# tc264_miniv3_1.net
KiCad netlist of a schematic drawn in EasyEDA Pro
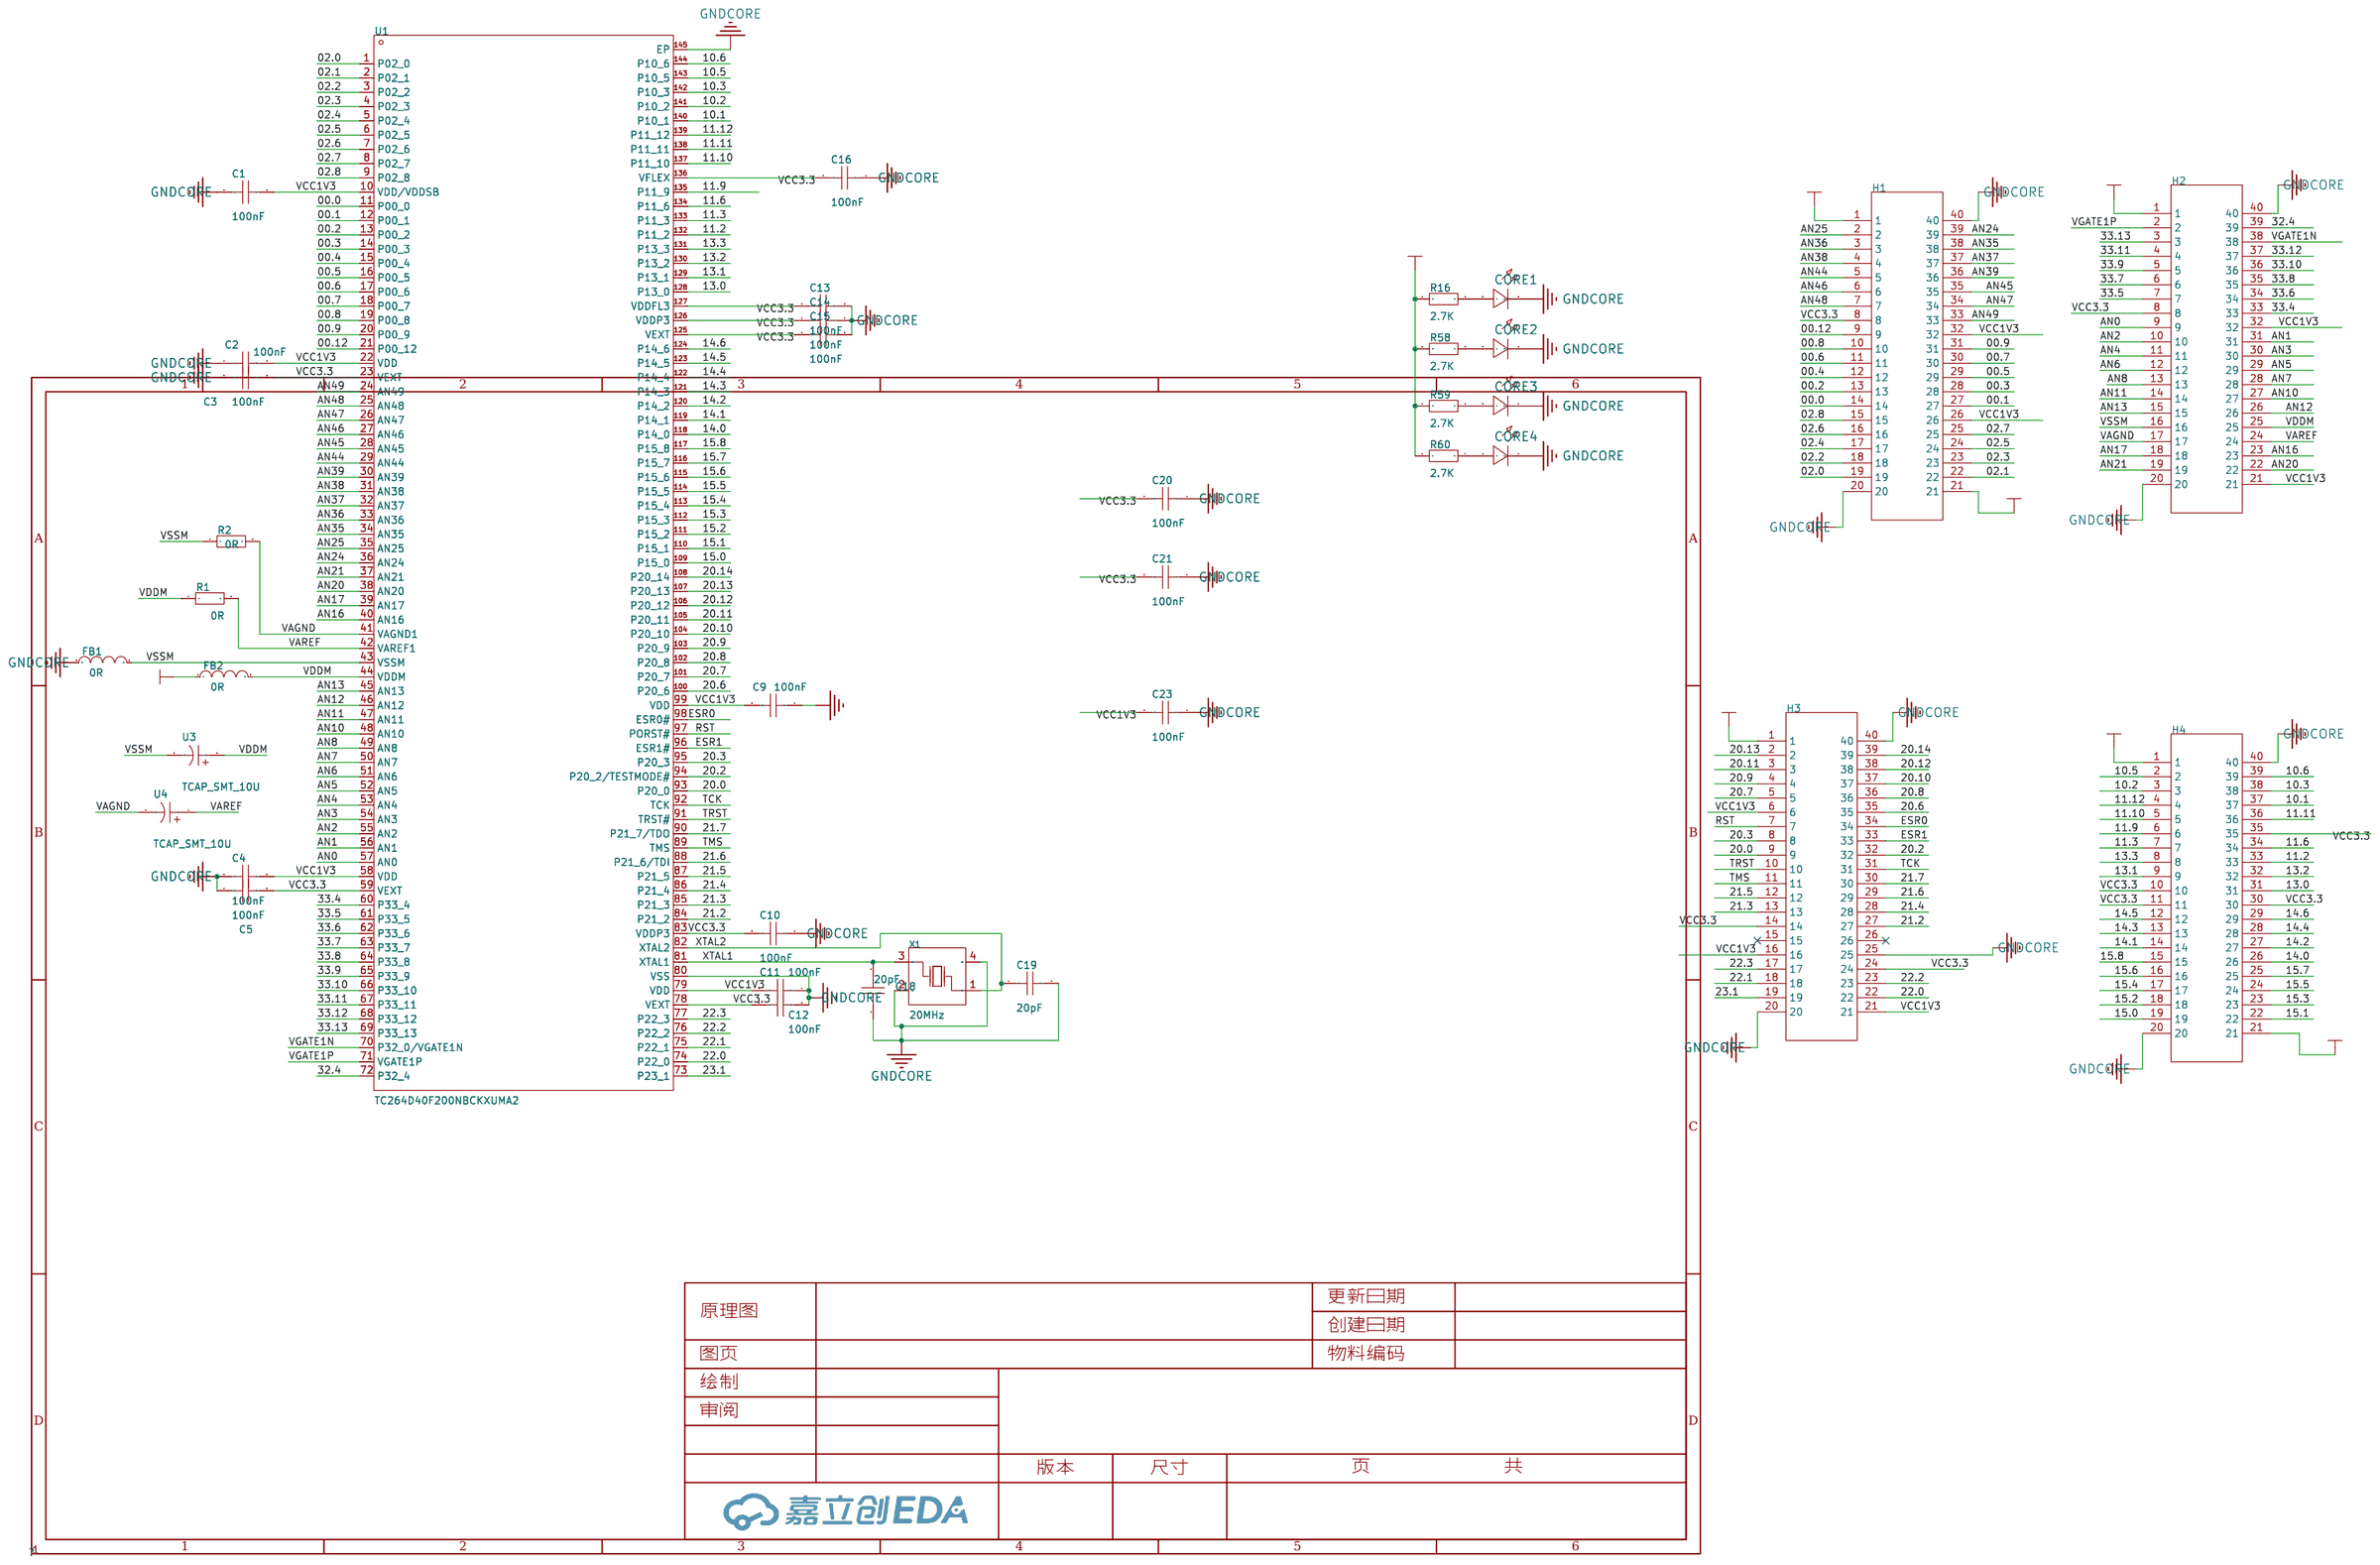
[diagram p0: schematic sheet]

(export (version "E")
  (design (tool "Eeschema 10.0.6"))
  (components
    (comp (ref "C1")
      (value "100nF")
      (footprint "easyedapro:C0603")
      (libsource (lib "easyedapro") (part "CapAcitance"))
    )
    (comp (ref "C2")
      (value "100nF")
      (footprint "easyedapro:C0603")
      (libsource (lib "easyedapro") (part "CapAcitance"))
    )
    (comp (ref "C3")
      (value "100nF")
      (footprint "easyedapro:C0603")
      (libsource (lib "easyedapro") (part "CapAcitance"))
    )
    (comp (ref "C4")
      (value "100nF")
      (footprint "easyedapro:C0603")
      (libsource (lib "easyedapro") (part "CapAcitance"))
    )
    (comp (ref "C5")
      (value "100nF")
      (footprint "easyedapro:C0603")
      (libsource (lib "easyedapro") (part "CapAcitance"))
    )
    (comp (ref "C9")
      (value "100nF")
      (footprint "easyedapro:C0603")
      (libsource (lib "easyedapro") (part "CapAcitance"))
    )
    (comp (ref "C10")
      (value "100nF")
      (footprint "easyedapro:C0603")
      (libsource (lib "easyedapro") (part "CapAcitance"))
    )
    (comp (ref "C11")
      (value "100nF")
      (footprint "easyedapro:C0603")
      (libsource (lib "easyedapro") (part "CapAcitance"))
    )
    (comp (ref "C12")
      (value "100nF")
      (footprint "easyedapro:C0603")
      (libsource (lib "easyedapro") (part "CapAcitance"))
    )
    (comp (ref "C13")
      (value "100nF")
      (footprint "easyedapro:C0603")
      (libsource (lib "easyedapro") (part "CapAcitance"))
    )
    (comp (ref "C14")
      (value "100nF")
      (footprint "easyedapro:C0603")
      (libsource (lib "easyedapro") (part "CapAcitance"))
    )
    (comp (ref "C15")
      (value "100nF")
      (footprint "easyedapro:C0603")
      (libsource (lib "easyedapro") (part "CapAcitance"))
    )
    (comp (ref "C16")
      (value "100nF")
      (footprint "easyedapro:C0603")
      (libsource (lib "easyedapro") (part "CapAcitance"))
    )
    (comp (ref "C18")
      (value "20pF")
      (footprint "easyedapro:C0603")
      (libsource (lib "easyedapro") (part "CapAcitance"))
    )
    (comp (ref "C19")
      (value "20pF")
      (footprint "easyedapro:C0603")
      (libsource (lib "easyedapro") (part "CapAcitance"))
    )
    (comp (ref "C20")
      (value "100nF")
      (footprint "easyedapro:C0603")
      (libsource (lib "easyedapro") (part "CapAcitance"))
    )
    (comp (ref "C21")
      (value "100nF")
      (footprint "easyedapro:C0603")
      (libsource (lib "easyedapro") (part "CapAcitance"))
    )
    (comp (ref "C23")
      (value "100nF")
      (footprint "easyedapro:C0603")
      (libsource (lib "easyedapro") (part "CapAcitance"))
    )
    (comp (ref "CORE1") (value "~") (libsource (lib "easyedapro") (part "LED_R")))
    (comp (ref "CORE2") (value "~") (libsource (lib "easyedapro") (part "LED_R")))
    (comp (ref "CORE3") (value "~") (libsource (lib "easyedapro") (part "LED_R")))
    (comp (ref "CORE4") (value "~") (libsource (lib "easyedapro") (part "LED_R")))
    (comp (ref "FB1")
      (value "0R")
      (footprint "easyedapro:L0603")
      (description "标称阻抗@测试频率:120Ω@100MHz;误差:±25%;直流电阻(RDC):50mΩ;额定电流:2A;电路数:1;")
      (fields (field (name "Manufacturer") "muRata(村田)"))
      (libsource (lib "easyedapro") (part "BLM18PG121SN1D_C14709"))
    )
    (comp (ref "FB2")
      (value "0R")
      (footprint "easyedapro:L0603")
      (description "标称阻抗@测试频率:120Ω@100MHz;误差:±25%;直流电阻(RDC):50mΩ;额定电流:2A;电路数:1;")
      (fields (field (name "Manufacturer") "muRata(村田)"))
      (libsource (lib "easyedapro") (part "BLM18PG121SN1D_C14709"))
    )
    (comp (ref "H1")
      (value "~")
      (footprint "easyedapro:HEADER_0.8mm_2x20P_G")
      (libsource (lib "easyedapro") (part "HEADER_0.8mm_2x20P_G"))
    )
    (comp (ref "H2")
      (value "~")
      (footprint "easyedapro:HEADER_0.8mm_2x20P_G")
      (libsource (lib "easyedapro") (part "HEADER_0.8mm_2x20P_G"))
    )
    (comp (ref "H3")
      (value "~")
      (footprint "easyedapro:HEADER_0.8mm_2x20P_G")
      (libsource (lib "easyedapro") (part "HEADER_0.8mm_2x20P_G"))
    )
    (comp (ref "H4")
      (value "~")
      (footprint "easyedapro:HEADER_0.8mm_2x20P_G")
      (libsource (lib "easyedapro") (part "HEADER_0.8mm_2x20P_G"))
    )
    (comp (ref "R1") (value "0R") (footprint "easyedapro:R0603") (libsource (lib "easyedapro") (part "电阻")))
    (comp (ref "R2") (value "0R") (footprint "easyedapro:R0603") (libsource (lib "easyedapro") (part "电阻")))
    (comp (ref "R16")
      (value "2.7K")
      (footprint "easyedapro:R0603")
      (libsource (lib "easyedapro") (part "电阻"))
    )
    (comp (ref "R58")
      (value "2.7K")
      (footprint "easyedapro:R0603")
      (libsource (lib "easyedapro") (part "电阻"))
    )
    (comp (ref "R59")
      (value "2.7K")
      (footprint "easyedapro:R0603")
      (libsource (lib "easyedapro") (part "电阻"))
    )
    (comp (ref "R60")
      (value "2.7K")
      (footprint "easyedapro:R0603")
      (libsource (lib "easyedapro") (part "电阻"))
    )
    (comp (ref "U1")
      (value "TC264D40F200NBCKXUMA2")
      (footprint "easyedapro:LQFP-144_L20.0-W20.0-P0.50-LS22.0-BL-EP6.7")
      (description "CPU内核:其他系列;CPU最大主频:20MHz;工作电压范围:3.3V~5V;GPIO端口数量:88;")
      (fields (field (name "Manufacturer") "Infineon(英飞凌)"))
      (libsource (lib "easyedapro") (part "TC264D40F200NBCKXUMA2"))
    )
    (comp (ref "U3")
      (value "TCAP_SMT_10U")
      (footprint "easyedapro:CAP-SMD_L3.2-W1.6-FD-1")
      (libsource (lib "easyedapro") (part "TCAP_SMT_10U"))
    )
    (comp (ref "U4")
      (value "TCAP_SMT_10U")
      (footprint "easyedapro:CAP-SMD_L3.2-W1.6-FD-1")
      (libsource (lib "easyedapro") (part "TCAP_SMT_10U"))
    )
    (comp (ref "X1")
      (value "20MHz")
      (footprint "easyedapro:OSC-SMD_4P-L3.2-W2.5-BL")
      (description "频率:12MHz;频率公差:±10ppm;负载电容:20pF;")
      (fields (field (name "Manufacturer Part") "X322512MSB4SI") (field (name "Manufacturer") "YXC(扬兴晶振)"))
      (libsource (lib "easyedapro") (part "X322512MSB4SI"))
    )
  )
  (nets
    (net (code "1") (name "/00.0") (class "Default")
      (node (ref "H1") (pin "14") (pinfunction "14_14") (pintype "input"))
      (node (ref "U1") (pin "11") (pinfunction "P00_0_11") (pintype "input"))
    )
    (net (code "2") (name "/00.1") (class "Default")
      (node (ref "H1") (pin "27") (pinfunction "27_27") (pintype "input"))
      (node (ref "U1") (pin "12") (pinfunction "P00_1_12") (pintype "input"))
    )
    (net (code "3") (name "/00.2") (class "Default")
      (node (ref "H1") (pin "13") (pinfunction "13_13") (pintype "input"))
      (node (ref "U1") (pin "13") (pinfunction "P00_2_13") (pintype "input"))
    )
    (net (code "4") (name "/00.3") (class "Default")
      (node (ref "H1") (pin "28") (pinfunction "28_28") (pintype "input"))
      (node (ref "U1") (pin "14") (pinfunction "P00_3_14") (pintype "input"))
    )
    (net (code "5") (name "/00.4") (class "Default")
      (node (ref "H1") (pin "12") (pinfunction "12_12") (pintype "input"))
      (node (ref "U1") (pin "15") (pinfunction "P00_4_15") (pintype "input"))
    )
    (net (code "6") (name "/00.5") (class "Default")
      (node (ref "H1") (pin "29") (pinfunction "29_29") (pintype "input"))
      (node (ref "U1") (pin "16") (pinfunction "P00_5_16") (pintype "input"))
    )
    (net (code "7") (name "/00.6") (class "Default")
      (node (ref "H1") (pin "11") (pinfunction "11_11") (pintype "input"))
      (node (ref "U1") (pin "17") (pinfunction "P00_6_17") (pintype "input"))
    )
    (net (code "8") (name "/00.7") (class "Default")
      (node (ref "H1") (pin "30") (pinfunction "30_30") (pintype "input"))
      (node (ref "U1") (pin "18") (pinfunction "P00_7_18") (pintype "input"))
    )
    (net (code "9") (name "/00.8") (class "Default")
      (node (ref "H1") (pin "10") (pinfunction "10_10") (pintype "input"))
      (node (ref "U1") (pin "19") (pinfunction "P00_8_19") (pintype "input"))
    )
    (net (code "10") (name "/00.9") (class "Default")
      (node (ref "H1") (pin "31") (pinfunction "31_31") (pintype "input"))
      (node (ref "U1") (pin "20") (pinfunction "P00_9_20") (pintype "input"))
    )
    (net (code "11") (name "/00.12") (class "Default")
      (node (ref "H1") (pin "9") (pinfunction "9_9") (pintype "input"))
      (node (ref "U1") (pin "21") (pinfunction "P00_12_21") (pintype "input"))
    )
    (net (code "12") (name "/02.0") (class "Default")
      (node (ref "H1") (pin "19") (pinfunction "19_19") (pintype "input"))
      (node (ref "U1") (pin "1") (pinfunction "P02_0_1") (pintype "input"))
    )
    (net (code "13") (name "/02.1") (class "Default")
      (node (ref "H1") (pin "22") (pinfunction "22_22") (pintype "input"))
      (node (ref "U1") (pin "2") (pinfunction "P02_1_2") (pintype "input"))
    )
    (net (code "14") (name "/02.2") (class "Default")
      (node (ref "H1") (pin "18") (pinfunction "18_18") (pintype "input"))
      (node (ref "U1") (pin "3") (pinfunction "P02_2_3") (pintype "input"))
    )
    (net (code "15") (name "/02.3") (class "Default")
      (node (ref "H1") (pin "23") (pinfunction "23_23") (pintype "input"))
      (node (ref "U1") (pin "4") (pinfunction "P02_3_4") (pintype "input"))
    )
    (net (code "16") (name "/02.4") (class "Default")
      (node (ref "H1") (pin "17") (pinfunction "17_17") (pintype "input"))
      (node (ref "U1") (pin "5") (pinfunction "P02_4_5") (pintype "input"))
    )
    (net (code "17") (name "/02.5") (class "Default")
      (node (ref "H1") (pin "24") (pinfunction "24_24") (pintype "input"))
      (node (ref "U1") (pin "6") (pinfunction "P02_5_6") (pintype "input"))
    )
    (net (code "18") (name "/02.6") (class "Default")
      (node (ref "H1") (pin "16") (pinfunction "16_16") (pintype "input"))
      (node (ref "U1") (pin "7") (pinfunction "P02_6_7") (pintype "input"))
    )
    (net (code "19") (name "/02.7") (class "Default")
      (node (ref "H1") (pin "25") (pinfunction "25_25") (pintype "input"))
      (node (ref "U1") (pin "8") (pinfunction "P02_7_8") (pintype "input"))
    )
    (net (code "20") (name "/02.8") (class "Default")
      (node (ref "H1") (pin "15") (pinfunction "15_15") (pintype "input"))
      (node (ref "U1") (pin "9") (pinfunction "P02_8_9") (pintype "input"))
    )
    (net (code "21") (name "/10.1") (class "Default")
      (node (ref "H4") (pin "37") (pinfunction "37_37") (pintype "input"))
      (node (ref "U1") (pin "140") (pinfunction "P10_1_140") (pintype "input"))
    )
    (net (code "22") (name "/10.2") (class "Default")
      (node (ref "H4") (pin "3") (pinfunction "3_3") (pintype "input"))
      (node (ref "U1") (pin "141") (pinfunction "P10_2_141") (pintype "input"))
    )
    (net (code "23") (name "/10.3") (class "Default")
      (node (ref "H4") (pin "38") (pinfunction "38_38") (pintype "input"))
      (node (ref "U1") (pin "142") (pinfunction "P10_3_142") (pintype "input"))
    )
    (net (code "24") (name "/10.5") (class "Default")
      (node (ref "H4") (pin "2") (pinfunction "2_2") (pintype "input"))
      (node (ref "U1") (pin "143") (pinfunction "P10_5_143") (pintype "input"))
    )
    (net (code "25") (name "/10.6") (class "Default")
      (node (ref "H4") (pin "39") (pinfunction "39_39") (pintype "input"))
      (node (ref "U1") (pin "144") (pinfunction "P10_6_144") (pintype "input"))
    )
    (net (code "26") (name "/11.2") (class "Default")
      (node (ref "H4") (pin "33") (pinfunction "33_33") (pintype "input"))
      (node (ref "U1") (pin "132") (pinfunction "P11_2_132") (pintype "input"))
    )
    (net (code "27") (name "/11.3") (class "Default")
      (node (ref "H4") (pin "7") (pinfunction "7_7") (pintype "input"))
      (node (ref "U1") (pin "133") (pinfunction "P11_3_133") (pintype "input"))
    )
    (net (code "28") (name "/11.6") (class "Default")
      (node (ref "H4") (pin "34") (pinfunction "34_34") (pintype "input"))
      (node (ref "U1") (pin "134") (pinfunction "P11_6_134") (pintype "input"))
    )
    (net (code "29") (name "/11.9") (class "Default")
      (node (ref "H4") (pin "6") (pinfunction "6_6") (pintype "input"))
      (node (ref "U1") (pin "135") (pinfunction "P11_9_135") (pintype "input"))
    )
    (net (code "30") (name "/11.10") (class "Default")
      (node (ref "H4") (pin "5") (pinfunction "5_5") (pintype "input"))
      (node (ref "U1") (pin "137") (pinfunction "P11_10_137") (pintype "input"))
    )
    (net (code "31") (name "/11.11") (class "Default")
      (node (ref "H4") (pin "36") (pinfunction "36_36") (pintype "input"))
      (node (ref "U1") (pin "138") (pinfunction "P11_11_138") (pintype "input"))
    )
    (net (code "32") (name "/11.12") (class "Default")
      (node (ref "H4") (pin "4") (pinfunction "4_4") (pintype "input"))
      (node (ref "U1") (pin "139") (pinfunction "P11_12_139") (pintype "input"))
    )
    (net (code "33") (name "/13.0") (class "Default")
      (node (ref "H4") (pin "31") (pinfunction "31_31") (pintype "input"))
      (node (ref "U1") (pin "128") (pinfunction "P13_0_128") (pintype "input"))
    )
    (net (code "34") (name "/13.1") (class "Default")
      (node (ref "H4") (pin "9") (pinfunction "9_9") (pintype "input"))
      (node (ref "U1") (pin "129") (pinfunction "P13_1_129") (pintype "input"))
    )
    (net (code "35") (name "/13.2") (class "Default")
      (node (ref "H4") (pin "32") (pinfunction "32_32") (pintype "input"))
      (node (ref "U1") (pin "130") (pinfunction "P13_2_130") (pintype "input"))
    )
    (net (code "36") (name "/13.3") (class "Default")
      (node (ref "H4") (pin "8") (pinfunction "8_8") (pintype "input"))
      (node (ref "U1") (pin "131") (pinfunction "P13_3_131") (pintype "input"))
    )
    (net (code "37") (name "/14.0") (class "Default")
      (node (ref "H4") (pin "26") (pinfunction "26_26") (pintype "input"))
      (node (ref "U1") (pin "118") (pinfunction "P14_0_118") (pintype "input"))
    )
    (net (code "38") (name "/14.1") (class "Default")
      (node (ref "H4") (pin "14") (pinfunction "14_14") (pintype "input"))
      (node (ref "U1") (pin "119") (pinfunction "P14_1_119") (pintype "input"))
    )
    (net (code "39") (name "/14.2") (class "Default")
      (node (ref "H4") (pin "27") (pinfunction "27_27") (pintype "input"))
      (node (ref "U1") (pin "120") (pinfunction "P14_2_120") (pintype "input"))
    )
    (net (code "40") (name "/14.3") (class "Default")
      (node (ref "H4") (pin "13") (pinfunction "13_13") (pintype "input"))
      (node (ref "U1") (pin "121") (pinfunction "P14_3_121") (pintype "input"))
    )
    (net (code "41") (name "/14.4") (class "Default")
      (node (ref "H4") (pin "28") (pinfunction "28_28") (pintype "input"))
      (node (ref "U1") (pin "122") (pinfunction "P14_4_122") (pintype "input"))
    )
    (net (code "42") (name "/14.5") (class "Default")
      (node (ref "H4") (pin "12") (pinfunction "12_12") (pintype "input"))
      (node (ref "U1") (pin "123") (pinfunction "P14_5_123") (pintype "input"))
    )
    (net (code "43") (name "/14.6") (class "Default")
      (node (ref "H4") (pin "29") (pinfunction "29_29") (pintype "input"))
      (node (ref "U1") (pin "124") (pinfunction "P14_6_124") (pintype "input"))
    )
    (net (code "44") (name "/15.0") (class "Default")
      (node (ref "H4") (pin "19") (pinfunction "19_19") (pintype "input"))
      (node (ref "U1") (pin "109") (pinfunction "P15_0_109") (pintype "input"))
    )
    (net (code "45") (name "/15.1") (class "Default")
      (node (ref "H4") (pin "22") (pinfunction "22_22") (pintype "input"))
      (node (ref "U1") (pin "110") (pinfunction "P15_1_110") (pintype "input"))
    )
    (net (code "46") (name "/15.2") (class "Default")
      (node (ref "H4") (pin "18") (pinfunction "18_18") (pintype "input"))
      (node (ref "U1") (pin "111") (pinfunction "P15_2_111") (pintype "input"))
    )
    (net (code "47") (name "/15.3") (class "Default")
      (node (ref "H4") (pin "23") (pinfunction "23_23") (pintype "input"))
      (node (ref "U1") (pin "112") (pinfunction "P15_3_112") (pintype "input"))
    )
    (net (code "48") (name "/15.4") (class "Default")
      (node (ref "H4") (pin "17") (pinfunction "17_17") (pintype "input"))
      (node (ref "U1") (pin "113") (pinfunction "P15_4_113") (pintype "input"))
    )
    (net (code "49") (name "/15.5") (class "Default")
      (node (ref "H4") (pin "24") (pinfunction "24_24") (pintype "input"))
      (node (ref "U1") (pin "114") (pinfunction "P15_5_114") (pintype "input"))
    )
    (net (code "50") (name "/15.6") (class "Default")
      (node (ref "H4") (pin "16") (pinfunction "16_16") (pintype "input"))
      (node (ref "U1") (pin "115") (pinfunction "P15_6_115") (pintype "input"))
    )
    (net (code "51") (name "/15.7") (class "Default")
      (node (ref "H4") (pin "25") (pinfunction "25_25") (pintype "input"))
      (node (ref "U1") (pin "116") (pinfunction "P15_7_116") (pintype "input"))
    )
    (net (code "52") (name "/15.8") (class "Default")
      (node (ref "H4") (pin "15") (pinfunction "15_15") (pintype "input"))
      (node (ref "U1") (pin "117") (pinfunction "P15_8_117") (pintype "input"))
    )
    (net (code "53") (name "/20.0") (class "Default")
      (node (ref "H3") (pin "9") (pinfunction "9_9") (pintype "input"))
      (node (ref "U1") (pin "93") (pinfunction "P20_0_93") (pintype "input"))
    )
    (net (code "54") (name "/20.2") (class "Default")
      (node (ref "H3") (pin "32") (pinfunction "32_32") (pintype "input"))
      (node (ref "U1") (pin "94") (pinfunction "P20_2/TESTMODE#_94") (pintype "input"))
    )
    (net (code "55") (name "/20.3") (class "Default")
      (node (ref "H3") (pin "8") (pinfunction "8_8") (pintype "input"))
      (node (ref "U1") (pin "95") (pinfunction "P20_3_95") (pintype "input"))
    )
    (net (code "56") (name "/20.6") (class "Default")
      (node (ref "H3") (pin "35") (pinfunction "35_35") (pintype "input"))
      (node (ref "U1") (pin "100") (pinfunction "P20_6_100") (pintype "input"))
    )
    (net (code "57") (name "/20.7") (class "Default")
      (node (ref "H3") (pin "5") (pinfunction "5_5") (pintype "input"))
      (node (ref "U1") (pin "101") (pinfunction "P20_7_101") (pintype "input"))
    )
    (net (code "58") (name "/20.8") (class "Default")
      (node (ref "H3") (pin "36") (pinfunction "36_36") (pintype "input"))
      (node (ref "U1") (pin "102") (pinfunction "P20_8_102") (pintype "input"))
    )
    (net (code "59") (name "/20.9") (class "Default")
      (node (ref "H3") (pin "4") (pinfunction "4_4") (pintype "input"))
      (node (ref "U1") (pin "103") (pinfunction "P20_9_103") (pintype "input"))
    )
    (net (code "60") (name "/20.10") (class "Default")
      (node (ref "H3") (pin "37") (pinfunction "37_37") (pintype "input"))
      (node (ref "U1") (pin "104") (pinfunction "P20_10_104") (pintype "input"))
    )
    (net (code "61") (name "/20.11") (class "Default")
      (node (ref "H3") (pin "3") (pinfunction "3_3") (pintype "input"))
      (node (ref "U1") (pin "105") (pinfunction "P20_11_105") (pintype "input"))
    )
    (net (code "62") (name "/20.12") (class "Default")
      (node (ref "H3") (pin "38") (pinfunction "38_38") (pintype "input"))
      (node (ref "U1") (pin "106") (pinfunction "P20_12_106") (pintype "input"))
    )
    (net (code "63") (name "/20.13") (class "Default")
      (node (ref "H3") (pin "2") (pinfunction "2_2") (pintype "input"))
      (node (ref "U1") (pin "107") (pinfunction "P20_13_107") (pintype "input"))
    )
    (net (code "64") (name "/20.14") (class "Default")
      (node (ref "H3") (pin "39") (pinfunction "39_39") (pintype "input"))
      (node (ref "U1") (pin "108") (pinfunction "P20_14_108") (pintype "input"))
    )
    (net (code "65") (name "/21.2") (class "Default")
      (node (ref "H3") (pin "27") (pinfunction "27_27") (pintype "input"))
      (node (ref "U1") (pin "84") (pinfunction "P21_2_84") (pintype "input"))
    )
    (net (code "66") (name "/21.3") (class "Default")
      (node (ref "H3") (pin "13") (pinfunction "13_13") (pintype "input"))
      (node (ref "U1") (pin "85") (pinfunction "P21_3_85") (pintype "input"))
    )
    (net (code "67") (name "/21.4") (class "Default")
      (node (ref "H3") (pin "28") (pinfunction "28_28") (pintype "input"))
      (node (ref "U1") (pin "86") (pinfunction "P21_4_86") (pintype "input"))
    )
    (net (code "68") (name "/21.5") (class "Default")
      (node (ref "H3") (pin "12") (pinfunction "12_12") (pintype "input"))
      (node (ref "U1") (pin "87") (pinfunction "P21_5_87") (pintype "input"))
    )
    (net (code "69") (name "/21.6") (class "Default")
      (node (ref "H3") (pin "29") (pinfunction "29_29") (pintype "input"))
      (node (ref "U1") (pin "88") (pinfunction "P21_6/TDI_88") (pintype "input"))
    )
    (net (code "70") (name "/21.7") (class "Default")
      (node (ref "H3") (pin "30") (pinfunction "30_30") (pintype "input"))
      (node (ref "U1") (pin "90") (pinfunction "P21_7/TDO_90") (pintype "input"))
    )
    (net (code "71") (name "/22.0") (class "Default")
      (node (ref "H3") (pin "22") (pinfunction "22_22") (pintype "input"))
      (node (ref "U1") (pin "74") (pinfunction "P22_0_74") (pintype "input"))
    )
    (net (code "72") (name "/22.1") (class "Default")
      (node (ref "H3") (pin "18") (pinfunction "18_18") (pintype "input"))
      (node (ref "U1") (pin "75") (pinfunction "P22_1_75") (pintype "input"))
    )
    (net (code "73") (name "/22.2") (class "Default")
      (node (ref "H3") (pin "23") (pinfunction "23_23") (pintype "input"))
      (node (ref "U1") (pin "76") (pinfunction "P22_2_76") (pintype "input"))
    )
    (net (code "74") (name "/22.3") (class "Default")
      (node (ref "H3") (pin "17") (pinfunction "17_17") (pintype "input"))
      (node (ref "U1") (pin "77") (pinfunction "P22_3_77") (pintype "input"))
    )
    (net (code "75") (name "/23.1") (class "Default")
      (node (ref "H3") (pin "19") (pinfunction "19_19") (pintype "input"))
      (node (ref "U1") (pin "73") (pinfunction "P23_1_73") (pintype "input"))
    )
    (net (code "76") (name "/32.4") (class "Default")
      (node (ref "H2") (pin "39") (pinfunction "39_39") (pintype "input"))
      (node (ref "U1") (pin "72") (pinfunction "P32_4_72") (pintype "input"))
    )
    (net (code "77") (name "/33.4") (class "Default")
      (node (ref "H2") (pin "33") (pinfunction "33_33") (pintype "input"))
      (node (ref "U1") (pin "60") (pinfunction "P33_4_60") (pintype "input"))
    )
    (net (code "78") (name "/33.5") (class "Default")
      (node (ref "H2") (pin "7") (pinfunction "7_7") (pintype "input"))
      (node (ref "U1") (pin "61") (pinfunction "P33_5_61") (pintype "input"))
    )
    (net (code "79") (name "/33.6") (class "Default")
      (node (ref "H2") (pin "34") (pinfunction "34_34") (pintype "input"))
      (node (ref "U1") (pin "62") (pinfunction "P33_6_62") (pintype "input"))
    )
    (net (code "80") (name "/33.7") (class "Default")
      (node (ref "H2") (pin "6") (pinfunction "6_6") (pintype "input"))
      (node (ref "U1") (pin "63") (pinfunction "P33_7_63") (pintype "input"))
    )
    (net (code "81") (name "/33.8") (class "Default")
      (node (ref "H2") (pin "35") (pinfunction "35_35") (pintype "input"))
      (node (ref "U1") (pin "64") (pinfunction "P33_8_64") (pintype "input"))
    )
    (net (code "82") (name "/33.9") (class "Default")
      (node (ref "H2") (pin "5") (pinfunction "5_5") (pintype "input"))
      (node (ref "U1") (pin "65") (pinfunction "P33_9_65") (pintype "input"))
    )
    (net (code "83") (name "/33.10") (class "Default")
      (node (ref "H2") (pin "36") (pinfunction "36_36") (pintype "input"))
      (node (ref "U1") (pin "66") (pinfunction "P33_10_66") (pintype "input"))
    )
    (net (code "84") (name "/33.11") (class "Default")
      (node (ref "H2") (pin "4") (pinfunction "4_4") (pintype "input"))
      (node (ref "U1") (pin "67") (pinfunction "P33_11_67") (pintype "input"))
    )
    (net (code "85") (name "/33.12") (class "Default")
      (node (ref "H2") (pin "37") (pinfunction "37_37") (pintype "input"))
      (node (ref "U1") (pin "68") (pinfunction "P33_12_68") (pintype "input"))
    )
    (net (code "86") (name "/33.13") (class "Default")
      (node (ref "H2") (pin "3") (pinfunction "3_3") (pintype "input"))
      (node (ref "U1") (pin "69") (pinfunction "P33_13_69") (pintype "input"))
    )
    (net (code "87") (name "/AN0") (class "Default")
      (node (ref "H2") (pin "9") (pinfunction "9_9") (pintype "input"))
      (node (ref "U1") (pin "57") (pinfunction "AN0_57") (pintype "input"))
    )
    (net (code "88") (name "/AN1") (class "Default")
      (node (ref "H2") (pin "31") (pinfunction "31_31") (pintype "input"))
      (node (ref "U1") (pin "56") (pinfunction "AN1_56") (pintype "input"))
    )
    (net (code "89") (name "/AN2") (class "Default")
      (node (ref "H2") (pin "10") (pinfunction "10_10") (pintype "input"))
      (node (ref "U1") (pin "55") (pinfunction "AN2_55") (pintype "input"))
    )
    (net (code "90") (name "/AN3") (class "Default")
      (node (ref "H2") (pin "30") (pinfunction "30_30") (pintype "input"))
      (node (ref "U1") (pin "54") (pinfunction "AN3_54") (pintype "input"))
    )
    (net (code "91") (name "/AN4") (class "Default")
      (node (ref "H2") (pin "11") (pinfunction "11_11") (pintype "input"))
      (node (ref "U1") (pin "53") (pinfunction "AN4_53") (pintype "input"))
    )
    (net (code "92") (name "/AN5") (class "Default")
      (node (ref "H2") (pin "29") (pinfunction "29_29") (pintype "input"))
      (node (ref "U1") (pin "52") (pinfunction "AN5_52") (pintype "input"))
    )
    (net (code "93") (name "/AN6") (class "Default")
      (node (ref "H2") (pin "12") (pinfunction "12_12") (pintype "input"))
      (node (ref "U1") (pin "51") (pinfunction "AN6_51") (pintype "input"))
    )
    (net (code "94") (name "/AN7") (class "Default")
      (node (ref "H2") (pin "28") (pinfunction "28_28") (pintype "input"))
      (node (ref "U1") (pin "50") (pinfunction "AN7_50") (pintype "input"))
    )
    (net (code "95") (name "/AN8") (class "Default")
      (node (ref "H2") (pin "13") (pinfunction "13_13") (pintype "input"))
      (node (ref "U1") (pin "49") (pinfunction "AN8_49") (pintype "input"))
    )
    (net (code "96") (name "/AN10") (class "Default")
      (node (ref "H2") (pin "27") (pinfunction "27_27") (pintype "input"))
      (node (ref "U1") (pin "48") (pinfunction "AN10_48") (pintype "input"))
    )
    (net (code "97") (name "/AN11") (class "Default")
      (node (ref "H2") (pin "14") (pinfunction "14_14") (pintype "input"))
      (node (ref "U1") (pin "47") (pinfunction "AN11_47") (pintype "input"))
    )
    (net (code "98") (name "/AN12") (class "Default")
      (node (ref "H2") (pin "26") (pinfunction "26_26") (pintype "input"))
      (node (ref "U1") (pin "46") (pinfunction "AN12_46") (pintype "input"))
    )
    (net (code "99") (name "/AN13") (class "Default")
      (node (ref "H2") (pin "15") (pinfunction "15_15") (pintype "input"))
      (node (ref "U1") (pin "45") (pinfunction "AN13_45") (pintype "input"))
    )
    (net (code "100") (name "/AN16") (class "Default")
      (node (ref "H2") (pin "23") (pinfunction "23_23") (pintype "input"))
      (node (ref "U1") (pin "40") (pinfunction "AN16_40") (pintype "input"))
    )
    (net (code "101") (name "/AN17") (class "Default")
      (node (ref "H2") (pin "18") (pinfunction "18_18") (pintype "input"))
      (node (ref "U1") (pin "39") (pinfunction "AN17_39") (pintype "input"))
    )
    (net (code "102") (name "/AN20") (class "Default")
      (node (ref "H2") (pin "22") (pinfunction "22_22") (pintype "input"))
      (node (ref "U1") (pin "38") (pinfunction "AN20_38") (pintype "input"))
    )
    (net (code "103") (name "/AN21") (class "Default")
      (node (ref "H2") (pin "19") (pinfunction "19_19") (pintype "input"))
      (node (ref "U1") (pin "37") (pinfunction "AN21_37") (pintype "input"))
    )
    (net (code "104") (name "/AN24") (class "Default")
      (node (ref "H1") (pin "39") (pinfunction "39_39") (pintype "input"))
      (node (ref "U1") (pin "36") (pinfunction "AN24_36") (pintype "input"))
    )
    (net (code "105") (name "/AN25") (class "Default")
      (node (ref "H1") (pin "2") (pinfunction "2_2") (pintype "input"))
      (node (ref "U1") (pin "35") (pinfunction "AN25_35") (pintype "input"))
    )
    (net (code "106") (name "/AN35") (class "Default")
      (node (ref "H1") (pin "38") (pinfunction "38_38") (pintype "input"))
      (node (ref "U1") (pin "34") (pinfunction "AN35_34") (pintype "input"))
    )
    (net (code "107") (name "/AN36") (class "Default")
      (node (ref "H1") (pin "3") (pinfunction "3_3") (pintype "input"))
      (node (ref "U1") (pin "33") (pinfunction "AN36_33") (pintype "input"))
    )
    (net (code "108") (name "/AN37") (class "Default")
      (node (ref "H1") (pin "37") (pinfunction "37_37") (pintype "input"))
      (node (ref "U1") (pin "32") (pinfunction "AN37_32") (pintype "input"))
    )
    (net (code "109") (name "/AN38") (class "Default")
      (node (ref "H1") (pin "4") (pinfunction "4_4") (pintype "input"))
      (node (ref "U1") (pin "31") (pinfunction "AN38_31") (pintype "input"))
    )
    (net (code "110") (name "/AN39") (class "Default")
      (node (ref "H1") (pin "36") (pinfunction "36_36") (pintype "input"))
      (node (ref "U1") (pin "30") (pinfunction "AN39_30") (pintype "input"))
    )
    (net (code "111") (name "/AN44") (class "Default")
      (node (ref "H1") (pin "5") (pinfunction "5_5") (pintype "input"))
      (node (ref "U1") (pin "29") (pinfunction "AN44_29") (pintype "input"))
    )
    (net (code "112") (name "/AN45") (class "Default")
      (node (ref "H1") (pin "35") (pinfunction "35_35") (pintype "input"))
      (node (ref "U1") (pin "28") (pinfunction "AN45_28") (pintype "input"))
    )
    (net (code "113") (name "/AN46") (class "Default")
      (node (ref "H1") (pin "6") (pinfunction "6_6") (pintype "input"))
      (node (ref "U1") (pin "27") (pinfunction "AN46_27") (pintype "input"))
    )
    (net (code "114") (name "/AN47") (class "Default")
      (node (ref "H1") (pin "34") (pinfunction "34_34") (pintype "input"))
      (node (ref "U1") (pin "26") (pinfunction "AN47_26") (pintype "input"))
    )
    (net (code "115") (name "/AN48") (class "Default")
      (node (ref "H1") (pin "7") (pinfunction "7_7") (pintype "input"))
      (node (ref "U1") (pin "25") (pinfunction "AN48_25") (pintype "input"))
    )
    (net (code "116") (name "/AN49") (class "Default")
      (node (ref "H1") (pin "33") (pinfunction "33_33") (pintype "input"))
      (node (ref "U1") (pin "24") (pinfunction "AN49_24") (pintype "input"))
    )
    (net (code "117") (name "/ESR0") (class "Default")
      (node (ref "H3") (pin "34") (pinfunction "34_34") (pintype "input"))
      (node (ref "U1") (pin "98") (pinfunction "ESR0#_98") (pintype "input"))
    )
    (net (code "118") (name "/ESR1") (class "Default")
      (node (ref "H3") (pin "33") (pinfunction "33_33") (pintype "input"))
      (node (ref "U1") (pin "96") (pinfunction "ESR1#_96") (pintype "input"))
    )
    (net (code "119") (name "/RST") (class "Default")
      (node (ref "H3") (pin "7") (pinfunction "7_7") (pintype "input"))
      (node (ref "U1") (pin "97") (pinfunction "PORST#_97") (pintype "input"))
    )
    (net (code "120") (name "/TCK") (class "Default")
      (node (ref "H3") (pin "31") (pinfunction "31_31") (pintype "input"))
      (node (ref "U1") (pin "92") (pinfunction "TCK_92") (pintype "input"))
    )
    (net (code "121") (name "/TMS") (class "Default")
      (node (ref "H3") (pin "11") (pinfunction "11_11") (pintype "input"))
      (node (ref "U1") (pin "89") (pinfunction "TMS_89") (pintype "input"))
    )
    (net (code "122") (name "/TRST") (class "Default")
      (node (ref "H3") (pin "10") (pinfunction "10_10") (pintype "input"))
      (node (ref "U1") (pin "91") (pinfunction "TRST#_91") (pintype "input"))
    )
    (net (code "123") (name "/VAGND") (class "Default")
      (node (ref "H2") (pin "17") (pinfunction "17_17") (pintype "input"))
      (node (ref "R2") (pin "2") (pinfunction "2_2") (pintype "input"))
      (node (ref "U1") (pin "41") (pinfunction "VAGND1_41") (pintype "input"))
      (node (ref "U4") (pin "2") (pinfunction "2_2") (pintype "input"))
    )
    (net (code "124") (name "/VAREF") (class "Default")
      (node (ref "H2") (pin "24") (pinfunction "24_24") (pintype "input"))
      (node (ref "R1") (pin "2") (pinfunction "2_2") (pintype "input"))
      (node (ref "U1") (pin "42") (pinfunction "VAREF1_42") (pintype "input"))
      (node (ref "U4") (pin "1") (pinfunction "1_1") (pintype "input"))
    )
    (net (code "125") (name "/VDDM") (class "Default")
      (node (ref "FB2") (pin "2") (pinfunction "2_2") (pintype "input"))
      (node (ref "H2") (pin "25") (pinfunction "25_25") (pintype "input"))
      (node (ref "R1") (pin "1") (pinfunction "1_1") (pintype "input"))
      (node (ref "U1") (pin "44") (pinfunction "VDDM_44") (pintype "input"))
      (node (ref "U3") (pin "1") (pinfunction "1_1") (pintype "input"))
    )
    (net (code "126") (name "/VGATE1N") (class "Default")
      (node (ref "H2") (pin "38") (pinfunction "38_38") (pintype "input"))
      (node (ref "U1") (pin "70") (pinfunction "P32_0/VGATE1N_70") (pintype "input"))
    )
    (net (code "127") (name "/VGATE1P") (class "Default")
      (node (ref "H2") (pin "2") (pinfunction "2_2") (pintype "input"))
      (node (ref "U1") (pin "71") (pinfunction "VGATE1P_71") (pintype "input"))
    )
    (net (code "128") (name "/VSSM") (class "Default")
      (node (ref "FB1") (pin "2") (pinfunction "2_2") (pintype "input"))
      (node (ref "H2") (pin "16") (pinfunction "16_16") (pintype "input"))
      (node (ref "R2") (pin "1") (pinfunction "1_1") (pintype "input"))
      (node (ref "U1") (pin "43") (pinfunction "VSSM_43") (pintype "input"))
      (node (ref "U3") (pin "2") (pinfunction "2_2") (pintype "input"))
    )
    (net (code "129") (name "/XTAL1") (class "Default")
      (node (ref "C18") (pin "2") (pinfunction "2_2") (pintype "input"))
      (node (ref "U1") (pin "81") (pinfunction "XTAL1_81") (pintype "input"))
      (node (ref "X1") (pin "3") (pinfunction "OSC2_3") (pintype "input"))
    )
    (net (code "130") (name "/XTAL2") (class "Default")
      (node (ref "C19") (pin "1") (pinfunction "1_1") (pintype "input"))
      (node (ref "U1") (pin "82") (pinfunction "XTAL2_82") (pintype "input"))
      (node (ref "X1") (pin "1") (pinfunction "OSC1_1") (pintype "input"))
    )
    (net (code "131") (name "GNDCORE") (class "Default")
      (node (ref "C1") (pin "1") (pinfunction "1_1") (pintype "input"))
      (node (ref "C10") (pin "1") (pinfunction "1_1") (pintype "input"))
      (node (ref "C11") (pin "1") (pinfunction "1_1") (pintype "input"))
      (node (ref "C12") (pin "1") (pinfunction "1_1") (pintype "input"))
      (node (ref "C13") (pin "1") (pinfunction "1_1") (pintype "input"))
      (node (ref "C14") (pin "1") (pinfunction "1_1") (pintype "input"))
      (node (ref "C15") (pin "1") (pinfunction "1_1") (pintype "input"))
      (node (ref "C16") (pin "1") (pinfunction "1_1") (pintype "input"))
      (node (ref "C18") (pin "1") (pinfunction "1_1") (pintype "input"))
      (node (ref "C19") (pin "2") (pinfunction "2_2") (pintype "input"))
      (node (ref "C2") (pin "1") (pinfunction "1_1") (pintype "input"))
      (node (ref "C20") (pin "1") (pinfunction "1_1") (pintype "input"))
      (node (ref "C21") (pin "1") (pinfunction "1_1") (pintype "input"))
      (node (ref "C23") (pin "1") (pinfunction "1_1") (pintype "input"))
      (node (ref "C3") (pin "1") (pinfunction "1_1") (pintype "input"))
      (node (ref "C4") (pin "1") (pinfunction "1_1") (pintype "input"))
      (node (ref "C5") (pin "1") (pinfunction "1_1") (pintype "input"))
      (node (ref "C9") (pin "1") (pinfunction "1_1") (pintype "input"))
      (node (ref "CORE1") (pin "1") (pinfunction "C_1") (pintype "input"))
      (node (ref "CORE2") (pin "1") (pinfunction "C_1") (pintype "input"))
      (node (ref "CORE3") (pin "1") (pinfunction "C_1") (pintype "input"))
      (node (ref "CORE4") (pin "1") (pinfunction "C_1") (pintype "input"))
      (node (ref "FB1") (pin "1") (pinfunction "1_1") (pintype "input"))
      (node (ref "H1") (pin "20") (pinfunction "20_20") (pintype "input"))
      (node (ref "H1") (pin "40") (pinfunction "40_40") (pintype "input"))
      (node (ref "H2") (pin "20") (pinfunction "20_20") (pintype "input"))
      (node (ref "H2") (pin "40") (pinfunction "40_40") (pintype "input"))
      (node (ref "H3") (pin "20") (pinfunction "20_20") (pintype "input"))
      (node (ref "H3") (pin "25") (pinfunction "25_25") (pintype "input"))
      (node (ref "H3") (pin "40") (pinfunction "40_40") (pintype "input"))
      (node (ref "H4") (pin "20") (pinfunction "20_20") (pintype "input"))
      (node (ref "H4") (pin "40") (pinfunction "40_40") (pintype "input"))
      (node (ref "U1") (pin "145") (pinfunction "EP_145") (pintype "input"))
      (node (ref "U1") (pin "80") (pinfunction "VSS_80") (pintype "input"))
      (node (ref "X1") (pin "2") (pinfunction "GND_2") (pintype "input"))
      (node (ref "X1") (pin "4") (pinfunction "GND_4") (pintype "input"))
    )
    (net (code "132") (name "Net-(CORE1-A)") (class "Default")
      (node (ref "CORE1") (pin "2") (pinfunction "A_2") (pintype "input"))
      (node (ref "R16") (pin "2") (pinfunction "2_2") (pintype "input"))
    )
    (net (code "133") (name "Net-(CORE2-A)") (class "Default")
      (node (ref "CORE2") (pin "2") (pinfunction "A_2") (pintype "input"))
      (node (ref "R58") (pin "2") (pinfunction "2_2") (pintype "input"))
    )
    (net (code "134") (name "Net-(CORE3-A)") (class "Default")
      (node (ref "CORE3") (pin "2") (pinfunction "A_2") (pintype "input"))
      (node (ref "R59") (pin "2") (pinfunction "2_2") (pintype "input"))
    )
    (net (code "135") (name "Net-(CORE4-A)") (class "Default")
      (node (ref "CORE4") (pin "2") (pinfunction "A_2") (pintype "input"))
      (node (ref "R60") (pin "2") (pinfunction "2_2") (pintype "input"))
    )
    (net (code "136") (name "VCC1V3") (class "Default")
      (node (ref "C1") (pin "2") (pinfunction "2_2") (pintype "input"))
      (node (ref "C11") (pin "2") (pinfunction "2_2") (pintype "input"))
      (node (ref "C2") (pin "2") (pinfunction "2_2") (pintype "input"))
      (node (ref "C23") (pin "2") (pinfunction "2_2") (pintype "input"))
      (node (ref "C4") (pin "2") (pinfunction "2_2") (pintype "input"))
      (node (ref "C9") (pin "2") (pinfunction "2_2") (pintype "input"))
      (node (ref "H1") (pin "26") (pinfunction "26_26") (pintype "input"))
      (node (ref "H1") (pin "32") (pinfunction "32_32") (pintype "input"))
      (node (ref "H2") (pin "1") (pinfunction "1_1") (pintype "input"))
      (node (ref "H2") (pin "21") (pinfunction "21_21") (pintype "input"))
      (node (ref "H2") (pin "32") (pinfunction "32_32") (pintype "input"))
      (node (ref "H3") (pin "16") (pinfunction "16_16") (pintype "input"))
      (node (ref "H3") (pin "21") (pinfunction "21_21") (pintype "input"))
      (node (ref "H3") (pin "6") (pinfunction "6_6") (pintype "input"))
      (node (ref "U1") (pin "10") (pinfunction "VDD/VDDSB_10") (pintype "input"))
      (node (ref "U1") (pin "22") (pinfunction "VDD_22") (pintype "input"))
      (node (ref "U1") (pin "58") (pinfunction "VDD_58") (pintype "input"))
      (node (ref "U1") (pin "79") (pinfunction "VDD_79") (pintype "input"))
      (node (ref "U1") (pin "99") (pinfunction "VDD_99") (pintype "input"))
    )
    (net (code "137") (name "VCC3.3") (class "Default")
      (node (ref "C10") (pin "2") (pinfunction "2_2") (pintype "input"))
      (node (ref "C12") (pin "2") (pinfunction "2_2") (pintype "input"))
      (node (ref "C13") (pin "2") (pinfunction "2_2") (pintype "input"))
      (node (ref "C14") (pin "2") (pinfunction "2_2") (pintype "input"))
      (node (ref "C15") (pin "2") (pinfunction "2_2") (pintype "input"))
      (node (ref "C16") (pin "2") (pinfunction "2_2") (pintype "input"))
      (node (ref "C20") (pin "2") (pinfunction "2_2") (pintype "input"))
      (node (ref "C21") (pin "2") (pinfunction "2_2") (pintype "input"))
      (node (ref "C3") (pin "2") (pinfunction "2_2") (pintype "input"))
      (node (ref "C5") (pin "2") (pinfunction "2_2") (pintype "input"))
      (node (ref "FB2") (pin "1") (pinfunction "1_1") (pintype "input"))
      (node (ref "H1") (pin "1") (pinfunction "1_1") (pintype "input"))
      (node (ref "H1") (pin "21") (pinfunction "21_21") (pintype "input"))
      (node (ref "H1") (pin "8") (pinfunction "8_8") (pintype "input"))
      (node (ref "H2") (pin "8") (pinfunction "8_8") (pintype "input"))
      (node (ref "H3") (pin "1") (pinfunction "1_1") (pintype "input"))
      (node (ref "H3") (pin "14") (pinfunction "14_14") (pintype "input"))
      (node (ref "H3") (pin "24") (pinfunction "24_24") (pintype "input"))
      (node (ref "H4") (pin "1") (pinfunction "1_1") (pintype "input"))
      (node (ref "H4") (pin "10") (pinfunction "10_10") (pintype "input"))
      (node (ref "H4") (pin "11") (pinfunction "11_11") (pintype "input"))
      (node (ref "H4") (pin "21") (pinfunction "21_21") (pintype "input"))
      (node (ref "H4") (pin "30") (pinfunction "30_30") (pintype "input"))
      (node (ref "H4") (pin "35") (pinfunction "35_35") (pintype "input"))
      (node (ref "R16") (pin "1") (pinfunction "1_1") (pintype "input"))
      (node (ref "R58") (pin "1") (pinfunction "1_1") (pintype "input"))
      (node (ref "R59") (pin "1") (pinfunction "1_1") (pintype "input"))
      (node (ref "R60") (pin "1") (pinfunction "1_1") (pintype "input"))
      (node (ref "U1") (pin "125") (pinfunction "VEXT_125") (pintype "input"))
      (node (ref "U1") (pin "126") (pinfunction "VDDP3_126") (pintype "input"))
      (node (ref "U1") (pin "127") (pinfunction "VDDFL3_127") (pintype "input"))
      (node (ref "U1") (pin "136") (pinfunction "VFLEX_136") (pintype "input"))
      (node (ref "U1") (pin "23") (pinfunction "VEXT_23") (pintype "input"))
      (node (ref "U1") (pin "59") (pinfunction "VEXT_59") (pintype "input"))
      (node (ref "U1") (pin "78") (pinfunction "VEXT_78") (pintype "input"))
      (node (ref "U1") (pin "83") (pinfunction "VDDP3_83") (pintype "input"))
    )
    (net (code "138") (name "unconnected-(H3-Pad15)") (class "Default")
      (node (ref "H3") (pin "15") (pinfunction "15_15") (pintype "input+no_connect"))
    )
    (net (code "139") (name "unconnected-(H3-Pad26)") (class "Default")
      (node (ref "H3") (pin "26") (pinfunction "26_26") (pintype "input+no_connect"))
    )
  )
)
